# 8-LEDx8.net
KiCad netlist of a schematic drawn in Altium Designer
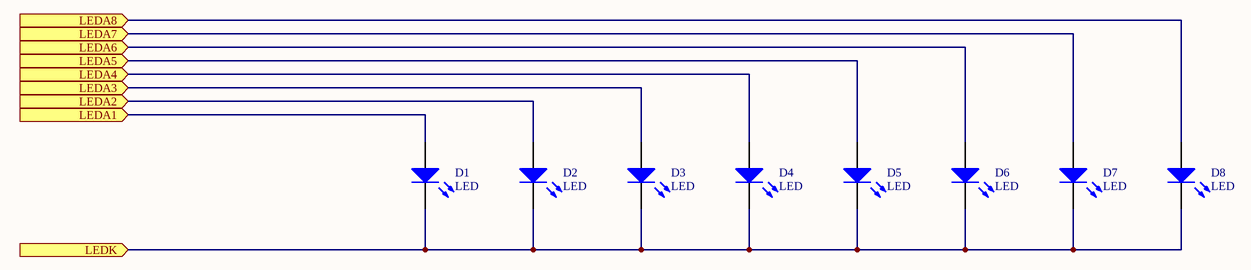
[diagram p0: 8-LEDx8.SchDoc]

(export (version "E")
  (design (tool "Eeschema 10.0.6"))
  (components
    (comp (ref "D1")
      (value "LED")
      (footprint "LED-3mm")
      (description "Diffused Green 3mm LED")
      (libsource (lib "Miscellaneous Devices") (part "LED0"))
    )
    (comp (ref "D2")
      (value "LED")
      (footprint "LED-3mm")
      (description "Diffused Green 3mm LED")
      (libsource (lib "Miscellaneous Devices") (part "LED0"))
    )
    (comp (ref "D3")
      (value "LED")
      (footprint "LED-3mm")
      (description "Diffused Green 3mm LED")
      (libsource (lib "Miscellaneous Devices") (part "LED0"))
    )
    (comp (ref "D4")
      (value "LED")
      (footprint "LED-3mm")
      (description "Diffused Green 3mm LED")
      (libsource (lib "Miscellaneous Devices") (part "LED0"))
    )
    (comp (ref "D5")
      (value "LED")
      (footprint "LED-3mm")
      (description "Diffused Green 3mm LED")
      (libsource (lib "Miscellaneous Devices") (part "LED0"))
    )
    (comp (ref "D6")
      (value "LED")
      (footprint "LED-3mm")
      (description "Diffused Green 3mm LED")
      (libsource (lib "Miscellaneous Devices") (part "LED0"))
    )
    (comp (ref "D7")
      (value "LED")
      (footprint "LED-3mm")
      (description "Diffused Green 3mm LED")
      (libsource (lib "Miscellaneous Devices") (part "LED0"))
    )
    (comp (ref "D8")
      (value "LED")
      (footprint "LED-3mm")
      (description "Diffused Green 3mm LED")
      (libsource (lib "Miscellaneous Devices") (part "LED0"))
    )
  )
  (nets
    (net (code "1") (name "/LEDA1") (class "Default")
      (node (ref "D1") (pin "1") (pinfunction "A_1") (pintype "passive"))
    )
    (net (code "2") (name "/LEDA2") (class "Default")
      (node (ref "D2") (pin "1") (pinfunction "A_1") (pintype "passive"))
    )
    (net (code "3") (name "/LEDA3") (class "Default")
      (node (ref "D3") (pin "1") (pinfunction "A_1") (pintype "passive"))
    )
    (net (code "4") (name "/LEDA4") (class "Default")
      (node (ref "D4") (pin "1") (pinfunction "A_1") (pintype "passive"))
    )
    (net (code "5") (name "/LEDA5") (class "Default")
      (node (ref "D5") (pin "1") (pinfunction "A_1") (pintype "passive"))
    )
    (net (code "6") (name "/LEDA6") (class "Default")
      (node (ref "D6") (pin "1") (pinfunction "A_1") (pintype "passive"))
    )
    (net (code "7") (name "/LEDA7") (class "Default")
      (node (ref "D7") (pin "1") (pinfunction "A_1") (pintype "passive"))
    )
    (net (code "8") (name "/LEDA8") (class "Default")
      (node (ref "D8") (pin "1") (pinfunction "A_1") (pintype "passive"))
    )
    (net (code "9") (name "/LEDK") (class "Default")
      (node (ref "D1") (pin "2") (pinfunction "K_2") (pintype "passive"))
      (node (ref "D2") (pin "2") (pinfunction "K_2") (pintype "passive"))
      (node (ref "D3") (pin "2") (pinfunction "K_2") (pintype "passive"))
      (node (ref "D4") (pin "2") (pinfunction "K_2") (pintype "passive"))
      (node (ref "D5") (pin "2") (pinfunction "K_2") (pintype "passive"))
      (node (ref "D6") (pin "2") (pinfunction "K_2") (pintype "passive"))
      (node (ref "D7") (pin "2") (pinfunction "K_2") (pintype "passive"))
      (node (ref "D8") (pin "2") (pinfunction "K_2") (pintype "passive"))
    )
  )
)
